# PCI_Driver_Shield_v9001.net
KiCad netlist of a schematic drawn in EAGLE
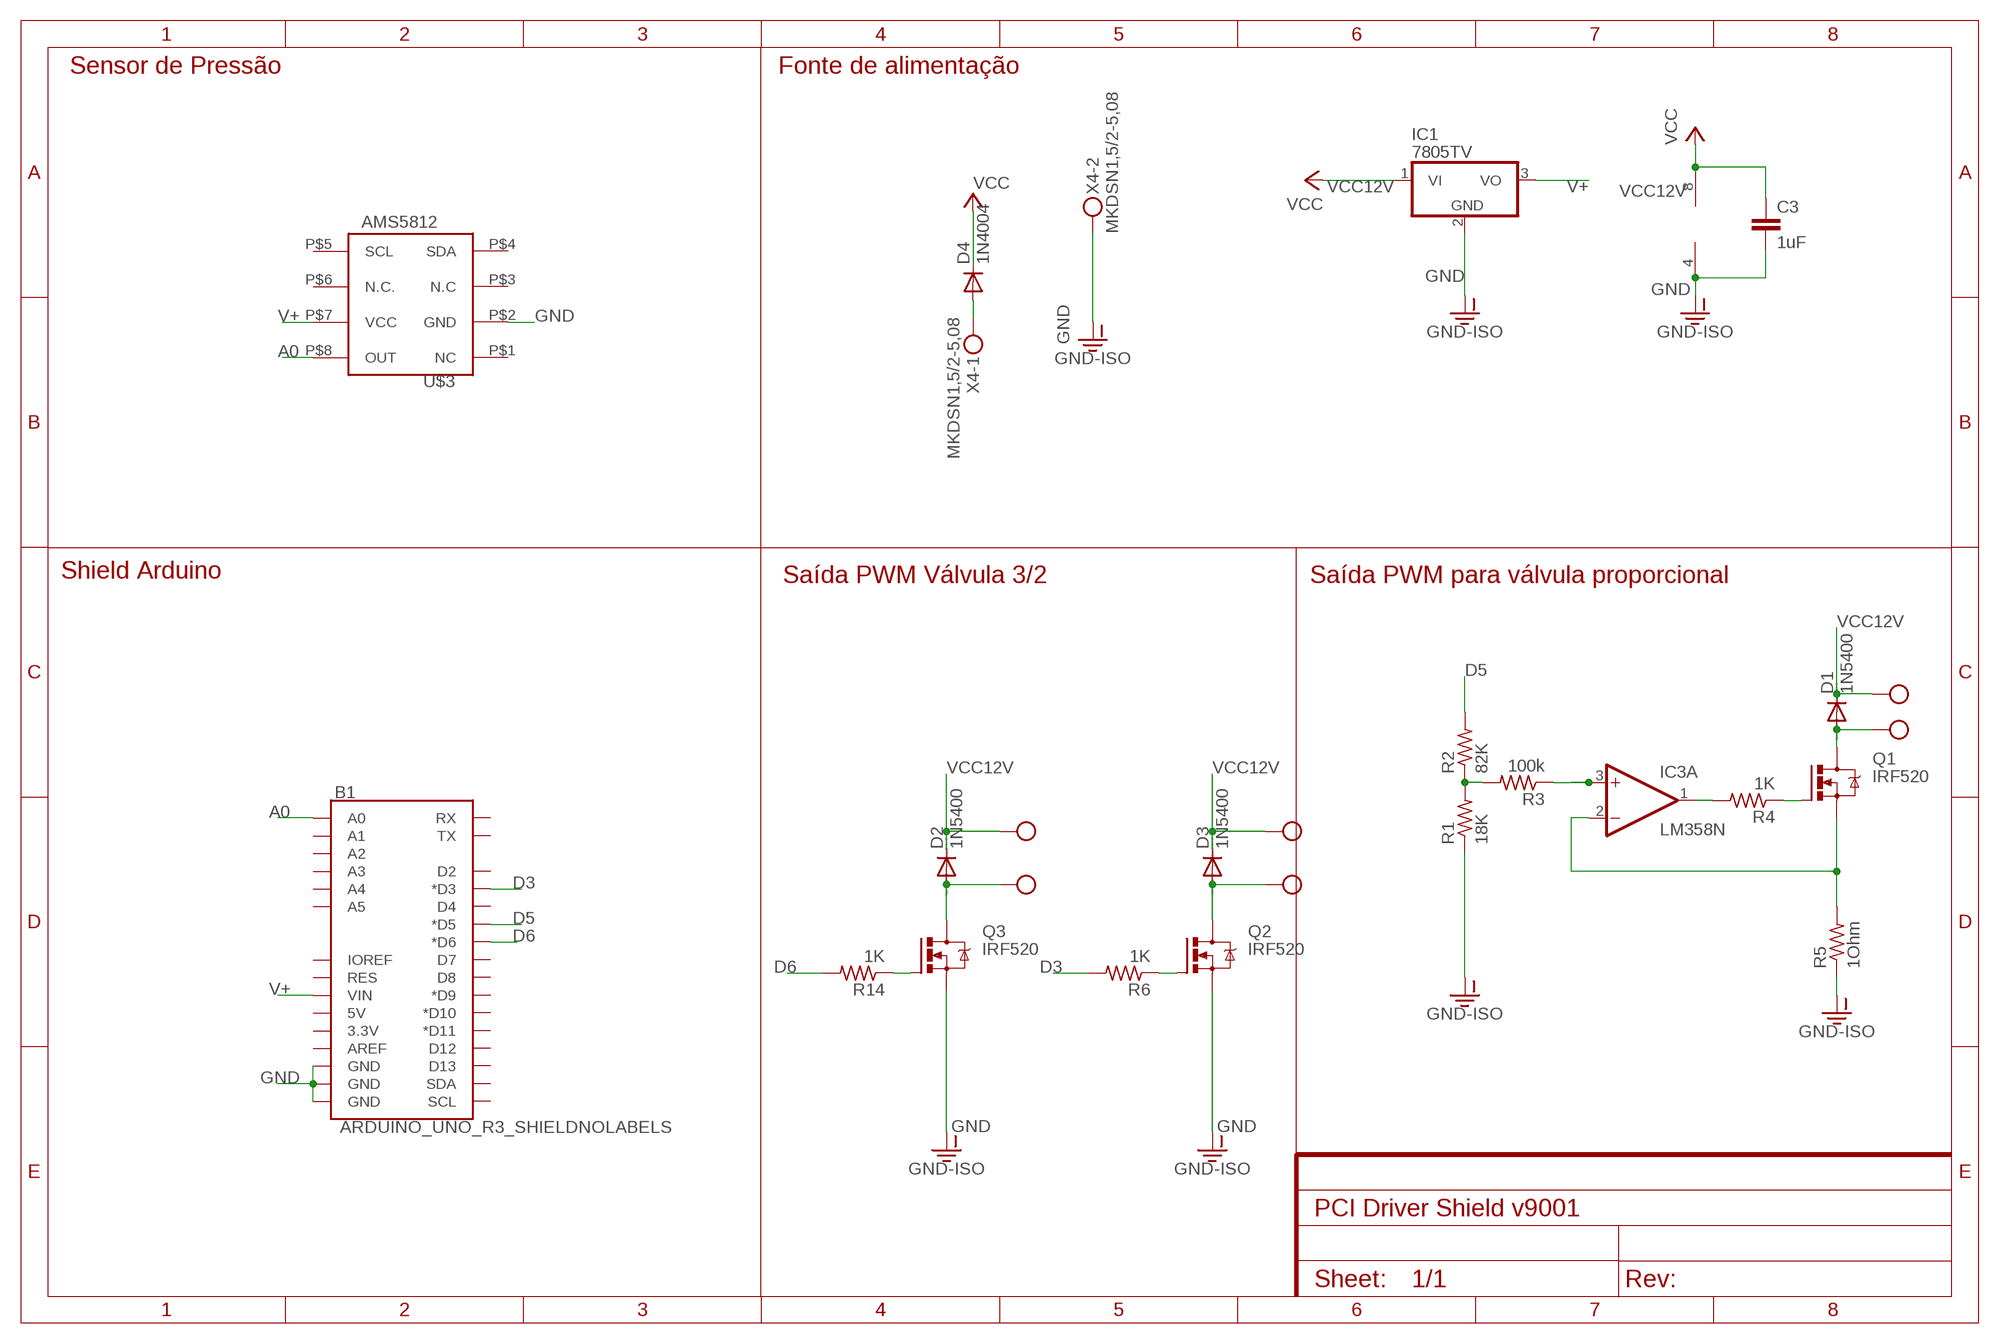
[diagram p0: schematic, sheet 1]

(export (version "E")
  (design (tool "Eeschema 10.0.6"))
  (components
    (comp (ref "B1")
      (value "ARDUINO_UNO_R3_SHIELDNOLABELS")
      (footprint "eagle-import:UNO_R3_SHIELD_NOLABELS")
      (libsource (lib "eagle-import") (part "ARDUINO_UNO_R3_SHIELDNOLABELS"))
    )
    (comp (ref "C3")
      (value "1uF")
      (footprint "eagle-import:C2.5-4")
      (libsource (lib "eagle-import") (part "C2.5/4"))
    )
    (comp (ref "D1")
      (value "1N5400")
      (footprint "eagle-import:DO201-15")
      (libsource (lib "eagle-import") (part "1N5400"))
    )
    (comp (ref "D2")
      (value "1N5400")
      (footprint "eagle-import:DO201-15")
      (libsource (lib "eagle-import") (part "1N5400"))
    )
    (comp (ref "D3")
      (value "1N5400")
      (footprint "eagle-import:DO201-15")
      (libsource (lib "eagle-import") (part "1N5400"))
    )
    (comp (ref "D4")
      (value "1N4004")
      (footprint "eagle-import:DO41-10")
      (libsource (lib "eagle-import") (part "1N4004"))
    )
    (comp (ref "IC1")
      (value "7805TV")
      (footprint "eagle-import:TO220V")
      (libsource (lib "eagle-import") (part "78TV05"))
    )
    (comp (ref "IC3")
      (value "LM358N")
      (footprint "eagle-import:DIL08")
      (fields (field (name "SPICEPREFIX") "J"))
      (libsource (lib "eagle-import") (part "LM358N"))
    )
    (comp (ref "Q1")
      (value "IRF520")
      (footprint "eagle-import:TO220BV")
      (fields (field (name "SPICEPREFIX") "Q"))
      (libsource (lib "eagle-import") (part "IRF520"))
    )
    (comp (ref "Q2")
      (value "IRF520")
      (footprint "eagle-import:TO220BV")
      (libsource (lib "eagle-import") (part "IRF520"))
    )
    (comp (ref "Q3")
      (value "IRF520")
      (footprint "eagle-import:TO220BV")
      (libsource (lib "eagle-import") (part "IRF520"))
    )
    (comp (ref "R1")
      (value "18K")
      (footprint "eagle-import:0204_7")
      (libsource (lib "eagle-import") (part "R-US_0204/7"))
    )
    (comp (ref "R2")
      (value "82K")
      (footprint "eagle-import:0204_7")
      (libsource (lib "eagle-import") (part "R-US_0204/7"))
    )
    (comp (ref "R3")
      (value "100k")
      (footprint "eagle-import:0204_7")
      (libsource (lib "eagle-import") (part "R-US_0204/7"))
    )
    (comp (ref "R4")
      (value "1K")
      (footprint "eagle-import:0204_7")
      (fields (field (name "SPICEPREFIX") "R"))
      (libsource (lib "eagle-import") (part "R-US_0204/7"))
    )
    (comp (ref "R5")
      (value "1Ohm")
      (footprint "eagle-import:0204_7")
      (libsource (lib "eagle-import") (part "R-US_0204/7"))
    )
    (comp (ref "R6")
      (value "1K")
      (footprint "eagle-import:0204_7")
      (libsource (lib "eagle-import") (part "R-US_0204/7"))
    )
    (comp (ref "R14")
      (value "1K")
      (footprint "eagle-import:0204_7")
      (libsource (lib "eagle-import") (part "R-US_0204/7"))
    )
    (comp (ref "S1")
      (value "MKDSN1,5/2-5,08")
      (footprint "eagle-import:MKDSN1,5_2-5,08")
      (libsource (lib "eagle-import") (part "MKDSN1,5/2-5,08"))
    )
    (comp (ref "S2")
      (value "MKDSN1,5/2-5,08")
      (footprint "eagle-import:MKDSN1,5_2-5,08")
      (libsource (lib "eagle-import") (part "MKDSN1,5/2-5,08"))
    )
    (comp (ref "S3")
      (value "MKDSN1,5/2-5,08")
      (footprint "eagle-import:MKDSN1,5_2-5,08")
      (libsource (lib "eagle-import") (part "MKDSN1,5/2-5,08"))
    )
    (comp (ref "U$3")
      (value "AMS5812")
      (footprint "eagle-import:AMS5812")
      (libsource (lib "eagle-import") (part "AMS5812"))
    )
    (comp (ref "X4")
      (value "MKDSN1,5/2-5,08")
      (footprint "eagle-import:MKDSN1,5_2-5,08")
      (libsource (lib "eagle-import") (part "MKDSN1,5/2-5,08"))
    )
  )
  (nets
    (net (code "1") (name "/A0") (class "Default")
      (node (ref "B1") (pin "A0") (pinfunction "A0_A0") (pintype "bidirectional"))
      (node (ref "U$3") (pin "P$8") (pinfunction "OUT_P$8") (pintype "output"))
    )
    (net (code "2") (name "/D3") (class "Default")
      (node (ref "B1") (pin "D3") (pinfunction "*D3_D3") (pintype "bidirectional"))
      (node (ref "R6") (pin "2") (pinfunction "2_2") (pintype "passive"))
    )
    (net (code "3") (name "/D5") (class "Default")
      (node (ref "B1") (pin "D5") (pinfunction "*D5_D5") (pintype "bidirectional"))
      (node (ref "R2") (pin "2") (pinfunction "2_2") (pintype "passive"))
    )
    (net (code "4") (name "/D6") (class "Default")
      (node (ref "B1") (pin "D6") (pinfunction "*D6_D6") (pintype "bidirectional"))
      (node (ref "R14") (pin "2") (pinfunction "2_2") (pintype "passive"))
    )
    (net (code "5") (name "/V+") (class "Default")
      (node (ref "B1") (pin "VIN") (pinfunction "VIN_VIN") (pintype "bidirectional"))
      (node (ref "IC1") (pin "3") (pinfunction "VO_3") (pintype "passive"))
      (node (ref "U$3") (pin "P$7") (pinfunction "VCC_P$7") (pintype "power_in"))
    )
    (net (code "6") (name "GND-ISO") (class "Default")
      (node (ref "B1") (pin "GND@0") (pinfunction "GND_GND@0") (pintype "bidirectional"))
      (node (ref "B1") (pin "GND@1") (pinfunction "GND_GND@1") (pintype "bidirectional"))
      (node (ref "B1") (pin "GND@2") (pinfunction "GND_GND@2") (pintype "bidirectional"))
      (node (ref "C3") (pin "2") (pinfunction "2_2") (pintype "passive"))
      (node (ref "IC1") (pin "2") (pinfunction "GND_2") (pintype "passive"))
      (node (ref "IC3") (pin "4") (pinfunction "V-_4") (pintype "power_in"))
      (node (ref "Q2") (pin "S") (pinfunction "S_S") (pintype "passive"))
      (node (ref "Q3") (pin "S") (pinfunction "S_S") (pintype "passive"))
      (node (ref "R1") (pin "1") (pinfunction "1_1") (pintype "passive"))
      (node (ref "R5") (pin "1") (pinfunction "1_1") (pintype "passive"))
      (node (ref "U$3") (pin "P$2") (pinfunction "GND_P$2") (pintype "power_in"))
      (node (ref "X4") (pin "2") (pinfunction "KL_2") (pintype "passive"))
    )
    (net (code "7") (name "Net-(IC3A-+IN)") (class "Default")
      (node (ref "IC3") (pin "3") (pinfunction "+IN_3") (pintype "input"))
      (node (ref "R3") (pin "1") (pinfunction "1_1") (pintype "passive"))
    )
    (net (code "8") (name "Net-(IC3A--IN)") (class "Default")
      (node (ref "IC3") (pin "2") (pinfunction "-IN_2") (pintype "input"))
      (node (ref "Q1") (pin "S") (pinfunction "S_S") (pintype "passive"))
      (node (ref "R5") (pin "2") (pinfunction "2_2") (pintype "passive"))
    )
    (net (code "9") (name "Net-(IC3A-OUT)") (class "Default")
      (node (ref "IC3") (pin "1") (pinfunction "OUT_1") (pintype "output"))
      (node (ref "R4") (pin "2") (pinfunction "2_2") (pintype "passive"))
    )
    (net (code "10") (name "Net-(Q1-PadG)") (class "Default")
      (node (ref "Q1") (pin "G") (pinfunction "G_G") (pintype "passive"))
      (node (ref "R4") (pin "1") (pinfunction "1_1") (pintype "passive"))
    )
    (net (code "11") (name "Net-(Q2-PadG)") (class "Default")
      (node (ref "Q2") (pin "G") (pinfunction "G_G") (pintype "passive"))
      (node (ref "R6") (pin "1") (pinfunction "1_1") (pintype "passive"))
    )
    (net (code "12") (name "Net-(Q3-PadG)") (class "Default")
      (node (ref "Q3") (pin "G") (pinfunction "G_G") (pintype "passive"))
      (node (ref "R14") (pin "1") (pinfunction "1_1") (pintype "passive"))
    )
    (net (code "13") (name "Net-(R1-Pad2)") (class "Default")
      (node (ref "R1") (pin "2") (pinfunction "2_2") (pintype "passive"))
      (node (ref "R2") (pin "1") (pinfunction "1_1") (pintype "passive"))
      (node (ref "R3") (pin "2") (pinfunction "2_2") (pintype "passive"))
    )
    (net (code "14") (name "Net-(S1A-KL)") (class "Default")
      (node (ref "D1") (pin "A") (pinfunction "A_A") (pintype "passive"))
      (node (ref "Q1") (pin "D") (pinfunction "D_D") (pintype "passive"))
      (node (ref "S1") (pin "1") (pinfunction "KL_1") (pintype "passive"))
    )
    (net (code "15") (name "Net-(S2A-KL)") (class "Default")
      (node (ref "D2") (pin "A") (pinfunction "A_A") (pintype "passive"))
      (node (ref "Q3") (pin "D") (pinfunction "D_D") (pintype "passive"))
      (node (ref "S2") (pin "1") (pinfunction "KL_1") (pintype "passive"))
    )
    (net (code "16") (name "Net-(S3A-KL)") (class "Default")
      (node (ref "D3") (pin "A") (pinfunction "A_A") (pintype "passive"))
      (node (ref "Q2") (pin "D") (pinfunction "D_D") (pintype "passive"))
      (node (ref "S3") (pin "1") (pinfunction "KL_1") (pintype "passive"))
    )
    (net (code "17") (name "Net-(X4A-KL)") (class "Default")
      (node (ref "D4") (pin "A") (pinfunction "A_A") (pintype "passive"))
      (node (ref "X4") (pin "1") (pinfunction "KL_1") (pintype "passive"))
    )
    (net (code "18") (name "VCC") (class "Default")
      (node (ref "C3") (pin "1") (pinfunction "1_1") (pintype "passive"))
      (node (ref "D1") (pin "C") (pinfunction "C_C") (pintype "passive"))
      (node (ref "D2") (pin "C") (pinfunction "C_C") (pintype "passive"))
      (node (ref "D3") (pin "C") (pinfunction "C_C") (pintype "passive"))
      (node (ref "D4") (pin "C") (pinfunction "C_C") (pintype "passive"))
      (node (ref "IC1") (pin "1") (pinfunction "VI_1") (pintype "input"))
      (node (ref "IC3") (pin "8") (pinfunction "V+_8") (pintype "power_in"))
      (node (ref "S1") (pin "2") (pinfunction "KL_2") (pintype "passive"))
      (node (ref "S2") (pin "2") (pinfunction "KL_2") (pintype "passive"))
      (node (ref "S3") (pin "2") (pinfunction "KL_2") (pintype "passive"))
    )
    (net (code "19") (name "unconnected-(B1-*D9-PadD9)") (class "Default")
      (node (ref "B1") (pin "D9") (pinfunction "*D9_D9") (pintype "bidirectional"))
    )
    (net (code "20") (name "unconnected-(B1-*D10-PadD10)") (class "Default")
      (node (ref "B1") (pin "D10") (pinfunction "*D10_D10") (pintype "bidirectional"))
    )
    (net (code "21") (name "unconnected-(B1-*D11-PadD11)") (class "Default")
      (node (ref "B1") (pin "D11") (pinfunction "*D11_D11") (pintype "bidirectional"))
    )
    (net (code "22") (name "unconnected-(B1-Pad3.3V)") (class "Default")
      (node (ref "B1") (pin "3.3V") (pinfunction "3.3V_3.3V") (pintype "bidirectional"))
    )
    (net (code "23") (name "unconnected-(B1-Pad5V)") (class "Default")
      (node (ref "B1") (pin "5V") (pinfunction "5V_5V") (pintype "bidirectional"))
    )
    (net (code "24") (name "unconnected-(B1-PadA1)") (class "Default")
      (node (ref "B1") (pin "A1") (pinfunction "A1_A1") (pintype "bidirectional"))
    )
    (net (code "25") (name "unconnected-(B1-PadA2)") (class "Default")
      (node (ref "B1") (pin "A2") (pinfunction "A2_A2") (pintype "bidirectional"))
    )
    (net (code "26") (name "unconnected-(B1-PadA3)") (class "Default")
      (node (ref "B1") (pin "A3") (pinfunction "A3_A3") (pintype "bidirectional"))
    )
    (net (code "27") (name "unconnected-(B1-PadA4)") (class "Default")
      (node (ref "B1") (pin "A4") (pinfunction "A4_A4") (pintype "bidirectional"))
    )
    (net (code "28") (name "unconnected-(B1-PadA5)") (class "Default")
      (node (ref "B1") (pin "A5") (pinfunction "A5_A5") (pintype "bidirectional"))
    )
    (net (code "29") (name "unconnected-(B1-PadAREF)") (class "Default")
      (node (ref "B1") (pin "AREF") (pinfunction "AREF_AREF") (pintype "bidirectional"))
    )
    (net (code "30") (name "unconnected-(B1-PadD2)") (class "Default")
      (node (ref "B1") (pin "D2") (pinfunction "D2_D2") (pintype "bidirectional"))
    )
    (net (code "31") (name "unconnected-(B1-PadD4)") (class "Default")
      (node (ref "B1") (pin "D4") (pinfunction "D4_D4") (pintype "bidirectional"))
    )
    (net (code "32") (name "unconnected-(B1-PadD7)") (class "Default")
      (node (ref "B1") (pin "D7") (pinfunction "D7_D7") (pintype "bidirectional"))
    )
    (net (code "33") (name "unconnected-(B1-PadD8)") (class "Default")
      (node (ref "B1") (pin "D8") (pinfunction "D8_D8") (pintype "bidirectional"))
    )
    (net (code "34") (name "unconnected-(B1-PadD12)") (class "Default")
      (node (ref "B1") (pin "D12") (pinfunction "D12_D12") (pintype "bidirectional"))
    )
    (net (code "35") (name "unconnected-(B1-PadD13)") (class "Default")
      (node (ref "B1") (pin "D13") (pinfunction "D13_D13") (pintype "bidirectional"))
    )
    (net (code "36") (name "unconnected-(B1-PadIOREF)") (class "Default")
      (node (ref "B1") (pin "IOREF") (pinfunction "IOREF_IOREF") (pintype "bidirectional"))
    )
    (net (code "37") (name "unconnected-(B1-PadRES)") (class "Default")
      (node (ref "B1") (pin "RES") (pinfunction "RES_RES") (pintype "bidirectional"))
    )
    (net (code "38") (name "unconnected-(B1-PadRX)") (class "Default")
      (node (ref "B1") (pin "RX") (pinfunction "RX_RX") (pintype "bidirectional"))
    )
    (net (code "39") (name "unconnected-(B1-PadSCL)") (class "Default")
      (node (ref "B1") (pin "SCL") (pinfunction "SCL_SCL") (pintype "bidirectional"))
    )
    (net (code "40") (name "unconnected-(B1-PadSDA)") (class "Default")
      (node (ref "B1") (pin "SDA") (pinfunction "SDA_SDA") (pintype "bidirectional"))
    )
    (net (code "41") (name "unconnected-(B1-PadTX)") (class "Default")
      (node (ref "B1") (pin "TX") (pinfunction "TX_TX") (pintype "bidirectional"))
    )
    (net (code "42") (name "unconnected-(U$3-N.C-PadP$3)") (class "Default")
      (node (ref "U$3") (pin "P$3") (pinfunction "N.C_P$3") (pintype "no_connect"))
    )
    (net (code "43") (name "unconnected-(U$3-N.C.-PadP$6)") (class "Default")
      (node (ref "U$3") (pin "P$6") (pinfunction "N.C._P$6") (pintype "no_connect"))
    )
    (net (code "44") (name "unconnected-(U$3-NC-PadP$1)") (class "Default")
      (node (ref "U$3") (pin "P$1") (pinfunction "NC_P$1") (pintype "no_connect"))
    )
    (net (code "45") (name "unconnected-(U$3-SCL-PadP$5)") (class "Default")
      (node (ref "U$3") (pin "P$5") (pinfunction "SCL_P$5") (pintype "bidirectional"))
    )
    (net (code "46") (name "unconnected-(U$3-SDA-PadP$4)") (class "Default")
      (node (ref "U$3") (pin "P$4") (pinfunction "SDA_P$4") (pintype "bidirectional"))
    )
  )
)
